# Opamp_AH.net
KiCad netlist of a schematic drawn in Altium Designer
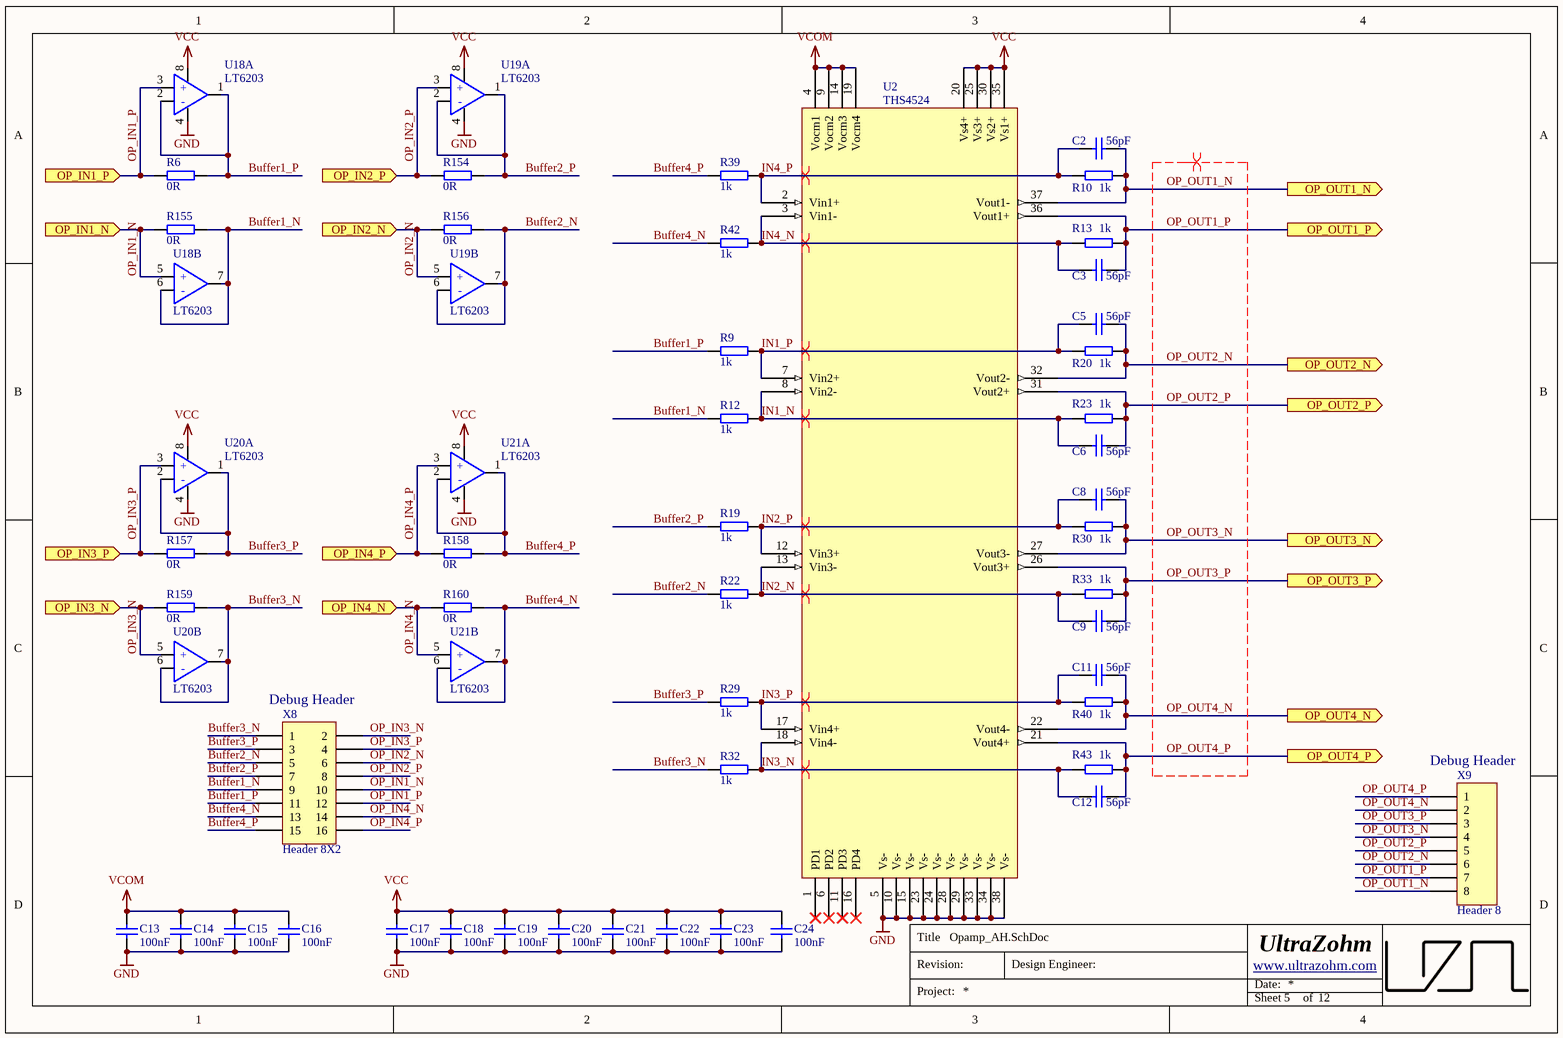
[diagram p0: Opamp_AH.SchDoc]

(export (version "E")
  (design (tool "Eeschema 10.0.6"))
  (components
    (comp (ref "C2")
      (value "56pF")
      (footprint "CAPC1608X07N")
      (fields
        (field (name "MF") "Vishay")
        (field (name "MPN") "VJ0603A560JXACW1BC")
        (field (name "VOLTAGE") "50V")
      )
      (libsource (lib "UltraZohm_ADC") (part "Cap_0603"))
    )
    (comp (ref "C3")
      (value "56pF")
      (footprint "CAPC1608X07N")
      (fields
        (field (name "MF") "Vishay")
        (field (name "MPN") "VJ0603A560JXACW1BC")
        (field (name "VOLTAGE") "50V")
      )
      (libsource (lib "UltraZohm_ADC") (part "Cap_0603"))
    )
    (comp (ref "C5")
      (value "56pF")
      (footprint "CAPC1608X07N")
      (fields
        (field (name "MF") "Vishay")
        (field (name "MPN") "VJ0603A560JXACW1BC")
        (field (name "VOLTAGE") "50V")
      )
      (libsource (lib "UltraZohm_ADC") (part "Cap_0603"))
    )
    (comp (ref "C6")
      (value "56pF")
      (footprint "CAPC1608X07N")
      (fields
        (field (name "MF") "Vishay")
        (field (name "MPN") "VJ0603A560JXACW1BC")
        (field (name "VOLTAGE") "50V")
      )
      (libsource (lib "UltraZohm_ADC") (part "Cap_0603"))
    )
    (comp (ref "C8")
      (value "56pF")
      (footprint "CAPC1608X07N")
      (fields
        (field (name "MF") "Vishay")
        (field (name "MPN") "VJ0603A560JXACW1BC")
        (field (name "VOLTAGE") "50V")
      )
      (libsource (lib "UltraZohm_ADC") (part "Cap_0603"))
    )
    (comp (ref "C9")
      (value "56pF")
      (footprint "CAPC1608X07N")
      (fields
        (field (name "MF") "Vishay")
        (field (name "MPN") "VJ0603A560JXACW1BC")
        (field (name "VOLTAGE") "50V")
      )
      (libsource (lib "UltraZohm_ADC") (part "Cap_0603"))
    )
    (comp (ref "C11")
      (value "56pF")
      (footprint "CAPC1608X07N")
      (fields
        (field (name "MF") "Vishay")
        (field (name "MPN") "VJ0603A560JXACW1BC")
        (field (name "VOLTAGE") "50V")
      )
      (libsource (lib "UltraZohm_ADC") (part "Cap_0603"))
    )
    (comp (ref "C12")
      (value "56pF")
      (footprint "CAPC1608X07N")
      (fields
        (field (name "MF") "Vishay")
        (field (name "MPN") "VJ0603A560JXACW1BC")
        (field (name "VOLTAGE") "50V")
      )
      (libsource (lib "UltraZohm_ADC") (part "Cap_0603"))
    )
    (comp (ref "C13")
      (value "100nF")
      (footprint "CAPC1608X07N")
      (fields (field (name "MF") "Würth") (field (name "MPN") "885012206071") (field (name "VOLTAGE") "25V"))
      (libsource (lib "UltraZohm_ADC") (part "Cap_0603"))
    )
    (comp (ref "C14")
      (value "100nF")
      (footprint "CAPC1608X07N")
      (fields (field (name "MF") "Würth") (field (name "MPN") "885012206071") (field (name "VOLTAGE") "25V"))
      (libsource (lib "UltraZohm_ADC") (part "Cap_0603"))
    )
    (comp (ref "C15")
      (value "100nF")
      (footprint "CAPC1608X07N")
      (fields (field (name "MF") "Würth") (field (name "MPN") "885012206071") (field (name "VOLTAGE") "25V"))
      (libsource (lib "UltraZohm_ADC") (part "Cap_0603"))
    )
    (comp (ref "C16")
      (value "100nF")
      (footprint "CAPC1608X07N")
      (fields (field (name "MF") "Würth") (field (name "MPN") "885012206071") (field (name "VOLTAGE") "25V"))
      (libsource (lib "UltraZohm_ADC") (part "Cap_0603"))
    )
    (comp (ref "C17")
      (value "100nF")
      (footprint "CAPC1608X07N")
      (fields (field (name "MF") "Würth") (field (name "MPN") "885012206071") (field (name "VOLTAGE") "25V"))
      (libsource (lib "UltraZohm_ADC") (part "Cap_0603"))
    )
    (comp (ref "C18")
      (value "100nF")
      (footprint "CAPC1608X07N")
      (fields (field (name "MF") "Würth") (field (name "MPN") "885012206071") (field (name "VOLTAGE") "25V"))
      (libsource (lib "UltraZohm_ADC") (part "Cap_0603"))
    )
    (comp (ref "C19")
      (value "100nF")
      (footprint "CAPC1608X07N")
      (fields (field (name "MF") "Würth") (field (name "MPN") "885012206071") (field (name "VOLTAGE") "25V"))
      (libsource (lib "UltraZohm_ADC") (part "Cap_0603"))
    )
    (comp (ref "C20")
      (value "100nF")
      (footprint "CAPC1608X07N")
      (fields (field (name "MF") "Würth") (field (name "MPN") "885012206071") (field (name "VOLTAGE") "25V"))
      (libsource (lib "UltraZohm_ADC") (part "Cap_0603"))
    )
    (comp (ref "C21")
      (value "100nF")
      (footprint "CAPC1608X07N")
      (fields (field (name "MF") "Würth") (field (name "MPN") "885012206071") (field (name "VOLTAGE") "25V"))
      (libsource (lib "UltraZohm_ADC") (part "Cap_0603"))
    )
    (comp (ref "C22")
      (value "100nF")
      (footprint "CAPC1608X07N")
      (fields (field (name "MF") "Würth") (field (name "MPN") "885012206071") (field (name "VOLTAGE") "25V"))
      (libsource (lib "UltraZohm_ADC") (part "Cap_0603"))
    )
    (comp (ref "C23")
      (value "100nF")
      (footprint "CAPC1608X07N")
      (fields (field (name "MF") "Würth") (field (name "MPN") "885012206071") (field (name "VOLTAGE") "25V"))
      (libsource (lib "UltraZohm_ADC") (part "Cap_0603"))
    )
    (comp (ref "C24")
      (value "100nF")
      (footprint "CAPC1608X07N")
      (fields (field (name "MF") "Würth") (field (name "MPN") "885012206071") (field (name "VOLTAGE") "25V"))
      (libsource (lib "UltraZohm_ADC") (part "Cap_0603"))
    )
    (comp (ref "R6")
      (value "0R")
      (footprint "RESC1608X06N")
      (fields (field (name "MF") "Vishay") (field (name "MPN") "CRCW06030000Z0EAC"))
      (libsource (lib "UltraZohm_ADC") (part "R_0603"))
    )
    (comp (ref "R9")
      (value "1k")
      (footprint "RESC1608X06N")
      (fields (field (name "MF") "Yageo") (field (name "MPN") "RC0603FR-071KL"))
      (libsource (lib "UltraZohm_ADC") (part "R_0603"))
    )
    (comp (ref "R10")
      (value "1k")
      (footprint "RESC1608X06N")
      (fields (field (name "MF") "Yageo") (field (name "MPN") "RC0603FR-071KL"))
      (libsource (lib "UltraZohm_ADC") (part "R_0603"))
    )
    (comp (ref "R12")
      (value "1k")
      (footprint "RESC1608X06N")
      (fields (field (name "MF") "Yageo") (field (name "MPN") "RC0603FR-071KL"))
      (libsource (lib "UltraZohm_ADC") (part "R_0603"))
    )
    (comp (ref "R13")
      (value "1k")
      (footprint "RESC1608X06N")
      (fields (field (name "MF") "Yageo") (field (name "MPN") "RC0603FR-071KL"))
      (libsource (lib "UltraZohm_ADC") (part "R_0603"))
    )
    (comp (ref "R19")
      (value "1k")
      (footprint "RESC1608X06N")
      (fields (field (name "MF") "Yageo") (field (name "MPN") "RC0603FR-071KL"))
      (libsource (lib "UltraZohm_ADC") (part "R_0603"))
    )
    (comp (ref "R20")
      (value "1k")
      (footprint "RESC1608X06N")
      (fields (field (name "MF") "Yageo") (field (name "MPN") "RC0603FR-071KL"))
      (libsource (lib "UltraZohm_ADC") (part "R_0603"))
    )
    (comp (ref "R22")
      (value "1k")
      (footprint "RESC1608X06N")
      (fields (field (name "MF") "Yageo") (field (name "MPN") "RC0603FR-071KL"))
      (libsource (lib "UltraZohm_ADC") (part "R_0603"))
    )
    (comp (ref "R23")
      (value "1k")
      (footprint "RESC1608X06N")
      (fields (field (name "MF") "Yageo") (field (name "MPN") "RC0603FR-071KL"))
      (libsource (lib "UltraZohm_ADC") (part "R_0603"))
    )
    (comp (ref "R29")
      (value "1k")
      (footprint "RESC1608X06N")
      (fields (field (name "MF") "Yageo") (field (name "MPN") "RC0603FR-071KL"))
      (libsource (lib "UltraZohm_ADC") (part "R_0603"))
    )
    (comp (ref "R30")
      (value "1k")
      (footprint "RESC1608X06N")
      (fields (field (name "MF") "Yageo") (field (name "MPN") "RC0603FR-071KL"))
      (libsource (lib "UltraZohm_ADC") (part "R_0603"))
    )
    (comp (ref "R32")
      (value "1k")
      (footprint "RESC1608X06N")
      (fields (field (name "MF") "Yageo") (field (name "MPN") "RC0603FR-071KL"))
      (libsource (lib "UltraZohm_ADC") (part "R_0805"))
    )
    (comp (ref "R33")
      (value "1k")
      (footprint "RESC1608X06N")
      (fields (field (name "MF") "Yageo") (field (name "MPN") "RC0603FR-071KL"))
      (libsource (lib "UltraZohm_ADC") (part "R_0603"))
    )
    (comp (ref "R39")
      (value "1k")
      (footprint "RESC1608X06N")
      (fields (field (name "MF") "Yageo") (field (name "MPN") "RC0603FR-071KL"))
      (libsource (lib "UltraZohm_ADC") (part "R_0603"))
    )
    (comp (ref "R40")
      (value "1k")
      (footprint "RESC1608X06N")
      (fields (field (name "MF") "Yageo") (field (name "MPN") "RC0603FR-071KL"))
      (libsource (lib "UltraZohm_ADC") (part "R_0603"))
    )
    (comp (ref "R42")
      (value "1k")
      (footprint "RESC1608X06N")
      (fields (field (name "MF") "Yageo") (field (name "MPN") "RC0603FR-071KL"))
      (libsource (lib "UltraZohm_ADC") (part "R_0603"))
    )
    (comp (ref "R43")
      (value "1k")
      (footprint "RESC1608X06N")
      (fields (field (name "MF") "Yageo") (field (name "MPN") "RC0603FR-071KL"))
      (libsource (lib "UltraZohm_ADC") (part "R_0603"))
    )
    (comp (ref "R154")
      (value "0R")
      (footprint "RESC1608X06N")
      (fields (field (name "MF") "Vishay") (field (name "MPN") "CRCW06030000Z0EAC"))
      (libsource (lib "UltraZohm_ADC") (part "R_0603"))
    )
    (comp (ref "R155")
      (value "0R")
      (footprint "RESC1608X06N")
      (fields (field (name "MF") "Vishay") (field (name "MPN") "CRCW06030000Z0EAC"))
      (libsource (lib "UltraZohm_ADC") (part "R_0603"))
    )
    (comp (ref "R156")
      (value "0R")
      (footprint "RESC1608X06N")
      (fields (field (name "MF") "Vishay") (field (name "MPN") "CRCW06030000Z0EAC"))
      (libsource (lib "UltraZohm_ADC") (part "R_0603"))
    )
    (comp (ref "R157")
      (value "0R")
      (footprint "RESC1608X06N")
      (fields (field (name "MF") "Vishay") (field (name "MPN") "CRCW06030000Z0EAC"))
      (libsource (lib "UltraZohm_ADC") (part "R_0603"))
    )
    (comp (ref "R158")
      (value "0R")
      (footprint "RESC1608X06N")
      (fields (field (name "MF") "Vishay") (field (name "MPN") "CRCW06030000Z0EAC"))
      (libsource (lib "UltraZohm_ADC") (part "R_0603"))
    )
    (comp (ref "R159")
      (value "0R")
      (footprint "RESC1608X06N")
      (fields (field (name "MF") "Vishay") (field (name "MPN") "CRCW06030000Z0EAC"))
      (libsource (lib "UltraZohm_ADC") (part "R_0603"))
    )
    (comp (ref "R160")
      (value "0R")
      (footprint "RESC1608X06N")
      (fields (field (name "MF") "Vishay") (field (name "MPN") "CRCW06030000Z0EAC"))
      (libsource (lib "UltraZohm_ADC") (part "R_0603"))
    )
    (comp (ref "U2")
      (value "THS4524")
      (footprint "TSSOP38")
      (fields (field (name "MF") "Texas Instruments") (field (name "MPN") "THS4524IDBTR"))
      (libsource (lib "UltraZohm_ADC") (part "THS4521"))
    )
    (comp (ref "U18")
      (value "LT6203")
      (footprint "8-MSOP")
      (description "IC OPAMP GP 2 CIRCUIT 8MSOP")
      (fields (field (name "MPN") "LT6203CMS8#PBF") (field (name "MF") "Analog Devices"))
      (libsource (lib "Componentes_SOC") (part "LT6203"))
    )
    (comp (ref "U19")
      (value "LT6203")
      (footprint "8-MSOP")
      (description "IC OPAMP GP 2 CIRCUIT 8MSOP")
      (fields (field (name "MPN") "LT6203CMS8#PBF") (field (name "MF") "Analog Devices"))
      (libsource (lib "Componentes_SOC") (part "LT6203"))
    )
    (comp (ref "U20")
      (value "LT6203")
      (footprint "8-MSOP")
      (description "IC OPAMP GP 2 CIRCUIT 8MSOP")
      (fields (field (name "MPN") "LT6203CMS8#PBF") (field (name "MF") "Analog Devices"))
      (libsource (lib "Componentes_SOC") (part "LT6203"))
    )
    (comp (ref "U21")
      (value "LT6203")
      (footprint "8-MSOP")
      (description "IC OPAMP GP 2 CIRCUIT 8MSOP")
      (fields (field (name "MPN") "LT6203CMS8#PBF") (field (name "MF") "Analog Devices"))
      (libsource (lib "Componentes_SOC") (part "LT6203"))
    )
    (comp (ref "X8")
      (value "Header 8X2")
      (footprint "HDR2X8")
      (description "Header, 8-Pin, Dual row")
      (fields (field (name "PUBLISHER") "Altium Limited"))
      (libsource (lib "Miscellaneous Connectors") (part "Header 8X2"))
    )
    (comp (ref "X9")
      (value "Header 8")
      (footprint "HDR1X8")
      (description "Header, 8-Pin")
      (fields (field (name "PUBLISHER") "Altium Limited"))
      (libsource (lib "Miscellaneous Connectors") (part "Header 8"))
    )
  )
  (nets
    (net (code "1") (name "/Buffer1_N") (class "Default")
      (node (ref "R12") (pin "2") (pintype "passive"))
      (node (ref "R155") (pin "2") (pintype "passive"))
      (node (ref "U18") (pin "6") (pinfunction "-_6") (pintype "passive"))
      (node (ref "U18") (pin "7") (pintype "passive"))
      (node (ref "X8") (pin "9") (pinfunction "9_9") (pintype "passive"))
    )
    (net (code "2") (name "/Buffer1_P") (class "Default")
      (node (ref "R6") (pin "2") (pintype "passive"))
      (node (ref "R9") (pin "1") (pintype "passive"))
      (node (ref "U18") (pin "1") (pintype "passive"))
      (node (ref "U18") (pin "2") (pinfunction "-_2") (pintype "passive"))
      (node (ref "X8") (pin "11") (pinfunction "11_11") (pintype "passive"))
    )
    (net (code "3") (name "/Buffer2_N") (class "Default")
      (node (ref "R156") (pin "2") (pintype "passive"))
      (node (ref "R22") (pin "2") (pintype "passive"))
      (node (ref "U19") (pin "6") (pinfunction "-_6") (pintype "passive"))
      (node (ref "U19") (pin "7") (pintype "passive"))
      (node (ref "X8") (pin "5") (pinfunction "5_5") (pintype "passive"))
    )
    (net (code "4") (name "/Buffer2_P") (class "Default")
      (node (ref "R154") (pin "2") (pintype "passive"))
      (node (ref "R19") (pin "1") (pintype "passive"))
      (node (ref "U19") (pin "1") (pintype "passive"))
      (node (ref "U19") (pin "2") (pinfunction "-_2") (pintype "passive"))
      (node (ref "X8") (pin "7") (pinfunction "7_7") (pintype "passive"))
    )
    (net (code "5") (name "/Buffer3_N") (class "Default")
      (node (ref "R159") (pin "2") (pintype "passive"))
      (node (ref "R32") (pin "2") (pintype "passive"))
      (node (ref "U20") (pin "6") (pinfunction "-_6") (pintype "passive"))
      (node (ref "U20") (pin "7") (pintype "passive"))
      (node (ref "X8") (pin "1") (pinfunction "1_1") (pintype "passive"))
    )
    (net (code "6") (name "/Buffer3_P") (class "Default")
      (node (ref "R157") (pin "2") (pintype "passive"))
      (node (ref "R29") (pin "1") (pintype "passive"))
      (node (ref "U20") (pin "1") (pintype "passive"))
      (node (ref "U20") (pin "2") (pinfunction "-_2") (pintype "passive"))
      (node (ref "X8") (pin "3") (pinfunction "3_3") (pintype "passive"))
    )
    (net (code "7") (name "/Buffer4_N") (class "Default")
      (node (ref "R160") (pin "2") (pintype "passive"))
      (node (ref "R42") (pin "2") (pintype "passive"))
      (node (ref "U21") (pin "6") (pinfunction "-_6") (pintype "passive"))
      (node (ref "U21") (pin "7") (pintype "passive"))
      (node (ref "X8") (pin "13") (pinfunction "13_13") (pintype "passive"))
    )
    (net (code "8") (name "/Buffer4_P") (class "Default")
      (node (ref "R158") (pin "2") (pintype "passive"))
      (node (ref "R39") (pin "1") (pintype "passive"))
      (node (ref "U21") (pin "1") (pintype "passive"))
      (node (ref "U21") (pin "2") (pinfunction "-_2") (pintype "passive"))
      (node (ref "X8") (pin "15") (pinfunction "15_15") (pintype "passive"))
    )
    (net (code "9") (name "/IN1_N") (class "Default")
      (node (ref "C6") (pin "1") (pinfunction "1_1") (pintype "passive"))
      (node (ref "R12") (pin "1") (pintype "passive"))
      (node (ref "R23") (pin "1") (pintype "passive"))
      (node (ref "U2") (pin "8") (pinfunction "Vin2-_8") (pintype "input"))
    )
    (net (code "10") (name "/IN1_P") (class "Default")
      (node (ref "C5") (pin "1") (pinfunction "1_1") (pintype "passive"))
      (node (ref "R20") (pin "1") (pintype "passive"))
      (node (ref "R9") (pin "2") (pintype "passive"))
      (node (ref "U2") (pin "7") (pinfunction "Vin2+_7") (pintype "input"))
    )
    (net (code "11") (name "/IN2_N") (class "Default")
      (node (ref "C9") (pin "1") (pinfunction "1_1") (pintype "passive"))
      (node (ref "R22") (pin "1") (pintype "passive"))
      (node (ref "R33") (pin "1") (pintype "passive"))
      (node (ref "U2") (pin "13") (pinfunction "Vin3-_13") (pintype "input"))
    )
    (net (code "12") (name "/IN2_P") (class "Default")
      (node (ref "C8") (pin "1") (pinfunction "1_1") (pintype "passive"))
      (node (ref "R19") (pin "2") (pintype "passive"))
      (node (ref "R30") (pin "1") (pintype "passive"))
      (node (ref "U2") (pin "12") (pinfunction "Vin3+_12") (pintype "input"))
    )
    (net (code "13") (name "/IN3_N") (class "Default")
      (node (ref "C12") (pin "1") (pinfunction "1_1") (pintype "passive"))
      (node (ref "R32") (pin "1") (pintype "passive"))
      (node (ref "R43") (pin "1") (pintype "passive"))
      (node (ref "U2") (pin "18") (pinfunction "Vin4-_18") (pintype "input"))
    )
    (net (code "14") (name "/IN3_P") (class "Default")
      (node (ref "C11") (pin "1") (pinfunction "1_1") (pintype "passive"))
      (node (ref "R29") (pin "2") (pintype "passive"))
      (node (ref "R40") (pin "1") (pintype "passive"))
      (node (ref "U2") (pin "17") (pinfunction "Vin4+_17") (pintype "input"))
    )
    (net (code "15") (name "/IN4_N") (class "Default")
      (node (ref "C3") (pin "1") (pinfunction "1_1") (pintype "passive"))
      (node (ref "R13") (pin "1") (pintype "passive"))
      (node (ref "R42") (pin "1") (pintype "passive"))
      (node (ref "U2") (pin "3") (pinfunction "Vin1-_3") (pintype "input"))
    )
    (net (code "16") (name "/IN4_P") (class "Default")
      (node (ref "C2") (pin "1") (pinfunction "1_1") (pintype "passive"))
      (node (ref "R10") (pin "1") (pintype "passive"))
      (node (ref "R39") (pin "2") (pintype "passive"))
      (node (ref "U2") (pin "2") (pinfunction "Vin1+_2") (pintype "input"))
    )
    (net (code "17") (name "/OP_IN1_N") (class "Default")
      (node (ref "R155") (pin "1") (pintype "passive"))
      (node (ref "U18") (pin "5") (pinfunction "+_5") (pintype "passive"))
      (node (ref "X8") (pin "10") (pinfunction "10_10") (pintype "passive"))
    )
    (net (code "18") (name "/OP_IN1_P") (class "Default")
      (node (ref "R6") (pin "1") (pintype "passive"))
      (node (ref "U18") (pin "3") (pinfunction "+_3") (pintype "passive"))
      (node (ref "X8") (pin "12") (pinfunction "12_12") (pintype "passive"))
    )
    (net (code "19") (name "/OP_IN2_N") (class "Default")
      (node (ref "R156") (pin "1") (pintype "passive"))
      (node (ref "U19") (pin "5") (pinfunction "+_5") (pintype "passive"))
      (node (ref "X8") (pin "6") (pinfunction "6_6") (pintype "passive"))
    )
    (net (code "20") (name "/OP_IN2_P") (class "Default")
      (node (ref "R154") (pin "1") (pintype "passive"))
      (node (ref "U19") (pin "3") (pinfunction "+_3") (pintype "passive"))
      (node (ref "X8") (pin "8") (pinfunction "8_8") (pintype "passive"))
    )
    (net (code "21") (name "/OP_IN3_N") (class "Default")
      (node (ref "R159") (pin "1") (pintype "passive"))
      (node (ref "U20") (pin "5") (pinfunction "+_5") (pintype "passive"))
      (node (ref "X8") (pin "2") (pinfunction "2_2") (pintype "passive"))
    )
    (net (code "22") (name "/OP_IN3_P") (class "Default")
      (node (ref "R157") (pin "1") (pintype "passive"))
      (node (ref "U20") (pin "3") (pinfunction "+_3") (pintype "passive"))
      (node (ref "X8") (pin "4") (pinfunction "4_4") (pintype "passive"))
    )
    (net (code "23") (name "/OP_IN4_N") (class "Default")
      (node (ref "R160") (pin "1") (pintype "passive"))
      (node (ref "U21") (pin "5") (pinfunction "+_5") (pintype "passive"))
      (node (ref "X8") (pin "14") (pinfunction "14_14") (pintype "passive"))
    )
    (net (code "24") (name "/OP_IN4_P") (class "Default")
      (node (ref "R158") (pin "1") (pintype "passive"))
      (node (ref "U21") (pin "3") (pinfunction "+_3") (pintype "passive"))
      (node (ref "X8") (pin "16") (pinfunction "16_16") (pintype "passive"))
    )
    (net (code "25") (name "/OP_OUT1_N") (class "Default")
      (node (ref "C2") (pin "2") (pinfunction "2_2") (pintype "passive"))
      (node (ref "R10") (pin "2") (pintype "passive"))
      (node (ref "U2") (pin "37") (pinfunction "Vout1-_37") (pintype "output"))
      (node (ref "X9") (pin "8") (pinfunction "8_8") (pintype "passive"))
    )
    (net (code "26") (name "/OP_OUT1_P") (class "Default")
      (node (ref "C3") (pin "2") (pinfunction "2_2") (pintype "passive"))
      (node (ref "R13") (pin "2") (pintype "passive"))
      (node (ref "U2") (pin "36") (pinfunction "Vout1+_36") (pintype "output"))
      (node (ref "X9") (pin "7") (pinfunction "7_7") (pintype "passive"))
    )
    (net (code "27") (name "/OP_OUT2_N") (class "Default")
      (node (ref "C5") (pin "2") (pinfunction "2_2") (pintype "passive"))
      (node (ref "R20") (pin "2") (pintype "passive"))
      (node (ref "U2") (pin "32") (pinfunction "Vout2-_32") (pintype "output"))
      (node (ref "X9") (pin "6") (pinfunction "6_6") (pintype "passive"))
    )
    (net (code "28") (name "/OP_OUT2_P") (class "Default")
      (node (ref "C6") (pin "2") (pinfunction "2_2") (pintype "passive"))
      (node (ref "R23") (pin "2") (pintype "passive"))
      (node (ref "U2") (pin "31") (pinfunction "Vout2+_31") (pintype "output"))
      (node (ref "X9") (pin "5") (pinfunction "5_5") (pintype "passive"))
    )
    (net (code "29") (name "/OP_OUT3_N") (class "Default")
      (node (ref "C8") (pin "2") (pinfunction "2_2") (pintype "passive"))
      (node (ref "R30") (pin "2") (pintype "passive"))
      (node (ref "U2") (pin "27") (pinfunction "Vout3-_27") (pintype "output"))
      (node (ref "X9") (pin "4") (pinfunction "4_4") (pintype "passive"))
    )
    (net (code "30") (name "/OP_OUT3_P") (class "Default")
      (node (ref "C9") (pin "2") (pinfunction "2_2") (pintype "passive"))
      (node (ref "R33") (pin "2") (pintype "passive"))
      (node (ref "U2") (pin "26") (pinfunction "Vout3+_26") (pintype "output"))
      (node (ref "X9") (pin "3") (pinfunction "3_3") (pintype "passive"))
    )
    (net (code "31") (name "/OP_OUT4_N") (class "Default")
      (node (ref "C11") (pin "2") (pinfunction "2_2") (pintype "passive"))
      (node (ref "R40") (pin "2") (pintype "passive"))
      (node (ref "U2") (pin "22") (pinfunction "Vout4-_22") (pintype "output"))
      (node (ref "X9") (pin "2") (pinfunction "2_2") (pintype "passive"))
    )
    (net (code "32") (name "/OP_OUT4_P") (class "Default")
      (node (ref "C12") (pin "2") (pinfunction "2_2") (pintype "passive"))
      (node (ref "R43") (pin "2") (pintype "passive"))
      (node (ref "U2") (pin "21") (pinfunction "Vout4+_21") (pintype "output"))
      (node (ref "X9") (pin "1") (pinfunction "1_1") (pintype "passive"))
    )
    (net (code "33") (name "GND") (class "Default")
      (node (ref "C13") (pin "2") (pinfunction "2_2") (pintype "passive"))
      (node (ref "C14") (pin "2") (pinfunction "2_2") (pintype "passive"))
      (node (ref "C15") (pin "2") (pinfunction "2_2") (pintype "passive"))
      (node (ref "C16") (pin "2") (pinfunction "2_2") (pintype "passive"))
      (node (ref "C17") (pin "2") (pinfunction "2_2") (pintype "passive"))
      (node (ref "C18") (pin "2") (pinfunction "2_2") (pintype "passive"))
      (node (ref "C19") (pin "2") (pinfunction "2_2") (pintype "passive"))
      (node (ref "C20") (pin "2") (pinfunction "2_2") (pintype "passive"))
      (node (ref "C21") (pin "2") (pinfunction "2_2") (pintype "passive"))
      (node (ref "C22") (pin "2") (pinfunction "2_2") (pintype "passive"))
      (node (ref "C23") (pin "2") (pinfunction "2_2") (pintype "passive"))
      (node (ref "C24") (pin "2") (pinfunction "2_2") (pintype "passive"))
      (node (ref "U18") (pin "4") (pintype "passive"))
      (node (ref "U19") (pin "4") (pintype "passive"))
      (node (ref "U2") (pin "10") (pinfunction "Vs-_10") (pintype "power_in"))
      (node (ref "U2") (pin "15") (pinfunction "Vs-_15") (pintype "power_in"))
      (node (ref "U2") (pin "23") (pinfunction "Vs-_23") (pintype "power_in"))
      (node (ref "U2") (pin "24") (pinfunction "Vs-_24") (pintype "power_in"))
      (node (ref "U2") (pin "28") (pinfunction "Vs-_28") (pintype "power_in"))
      (node (ref "U2") (pin "29") (pinfunction "Vs-_29") (pintype "power_in"))
      (node (ref "U2") (pin "33") (pinfunction "Vs-_33") (pintype "power_in"))
      (node (ref "U2") (pin "34") (pinfunction "Vs-_34") (pintype "power_in"))
      (node (ref "U2") (pin "38") (pinfunction "Vs-_38") (pintype "power_in"))
      (node (ref "U2") (pin "5") (pinfunction "Vs-_5") (pintype "power_in"))
      (node (ref "U20") (pin "4") (pintype "passive"))
      (node (ref "U21") (pin "4") (pintype "passive"))
    )
    (net (code "34") (name "VCC") (class "Default")
      (node (ref "C17") (pin "1") (pinfunction "1_1") (pintype "passive"))
      (node (ref "C18") (pin "1") (pinfunction "1_1") (pintype "passive"))
      (node (ref "C19") (pin "1") (pinfunction "1_1") (pintype "passive"))
      (node (ref "C20") (pin "1") (pinfunction "1_1") (pintype "passive"))
      (node (ref "C21") (pin "1") (pinfunction "1_1") (pintype "passive"))
      (node (ref "C22") (pin "1") (pinfunction "1_1") (pintype "passive"))
      (node (ref "C23") (pin "1") (pinfunction "1_1") (pintype "passive"))
      (node (ref "C24") (pin "1") (pinfunction "1_1") (pintype "passive"))
      (node (ref "U18") (pin "8") (pintype "passive"))
      (node (ref "U19") (pin "8") (pintype "passive"))
      (node (ref "U2") (pin "20") (pinfunction "Vs4+_20") (pintype "power_in"))
      (node (ref "U2") (pin "25") (pinfunction "Vs3+_25") (pintype "power_in"))
      (node (ref "U2") (pin "30") (pinfunction "Vs2+_30") (pintype "power_in"))
      (node (ref "U2") (pin "35") (pinfunction "Vs1+_35") (pintype "power_in"))
      (node (ref "U20") (pin "8") (pintype "passive"))
      (node (ref "U21") (pin "8") (pintype "passive"))
    )
    (net (code "35") (name "VCOM") (class "Default")
      (node (ref "C13") (pin "1") (pinfunction "1_1") (pintype "passive"))
      (node (ref "C14") (pin "1") (pinfunction "1_1") (pintype "passive"))
      (node (ref "C15") (pin "1") (pinfunction "1_1") (pintype "passive"))
      (node (ref "C16") (pin "1") (pinfunction "1_1") (pintype "passive"))
      (node (ref "U2") (pin "14") (pinfunction "Vocm3_14") (pintype "power_in"))
      (node (ref "U2") (pin "19") (pinfunction "Vocm4_19") (pintype "power_in"))
      (node (ref "U2") (pin "4") (pinfunction "Vocm1_4") (pintype "power_in"))
      (node (ref "U2") (pin "9") (pinfunction "Vocm2_9") (pintype "power_in"))
    )
    (net (code "36") (name "unconnected-(U2-PD1-Pad1)") (class "Default")
      (node (ref "U2") (pin "1") (pinfunction "PD1_1") (pintype "passive+no_connect"))
    )
    (net (code "37") (name "unconnected-(U2-PD2-Pad6)") (class "Default")
      (node (ref "U2") (pin "6") (pinfunction "PD2_6") (pintype "passive+no_connect"))
    )
    (net (code "38") (name "unconnected-(U2-PD3-Pad11)") (class "Default")
      (node (ref "U2") (pin "11") (pinfunction "PD3_11") (pintype "passive+no_connect"))
    )
    (net (code "39") (name "unconnected-(U2-PD4-Pad16)") (class "Default")
      (node (ref "U2") (pin "16") (pinfunction "PD4_16") (pintype "passive+no_connect"))
    )
  )
)
